# 3_Power_amp_Peripherals.net
KiCad netlist of a schematic drawn in Altium Designer
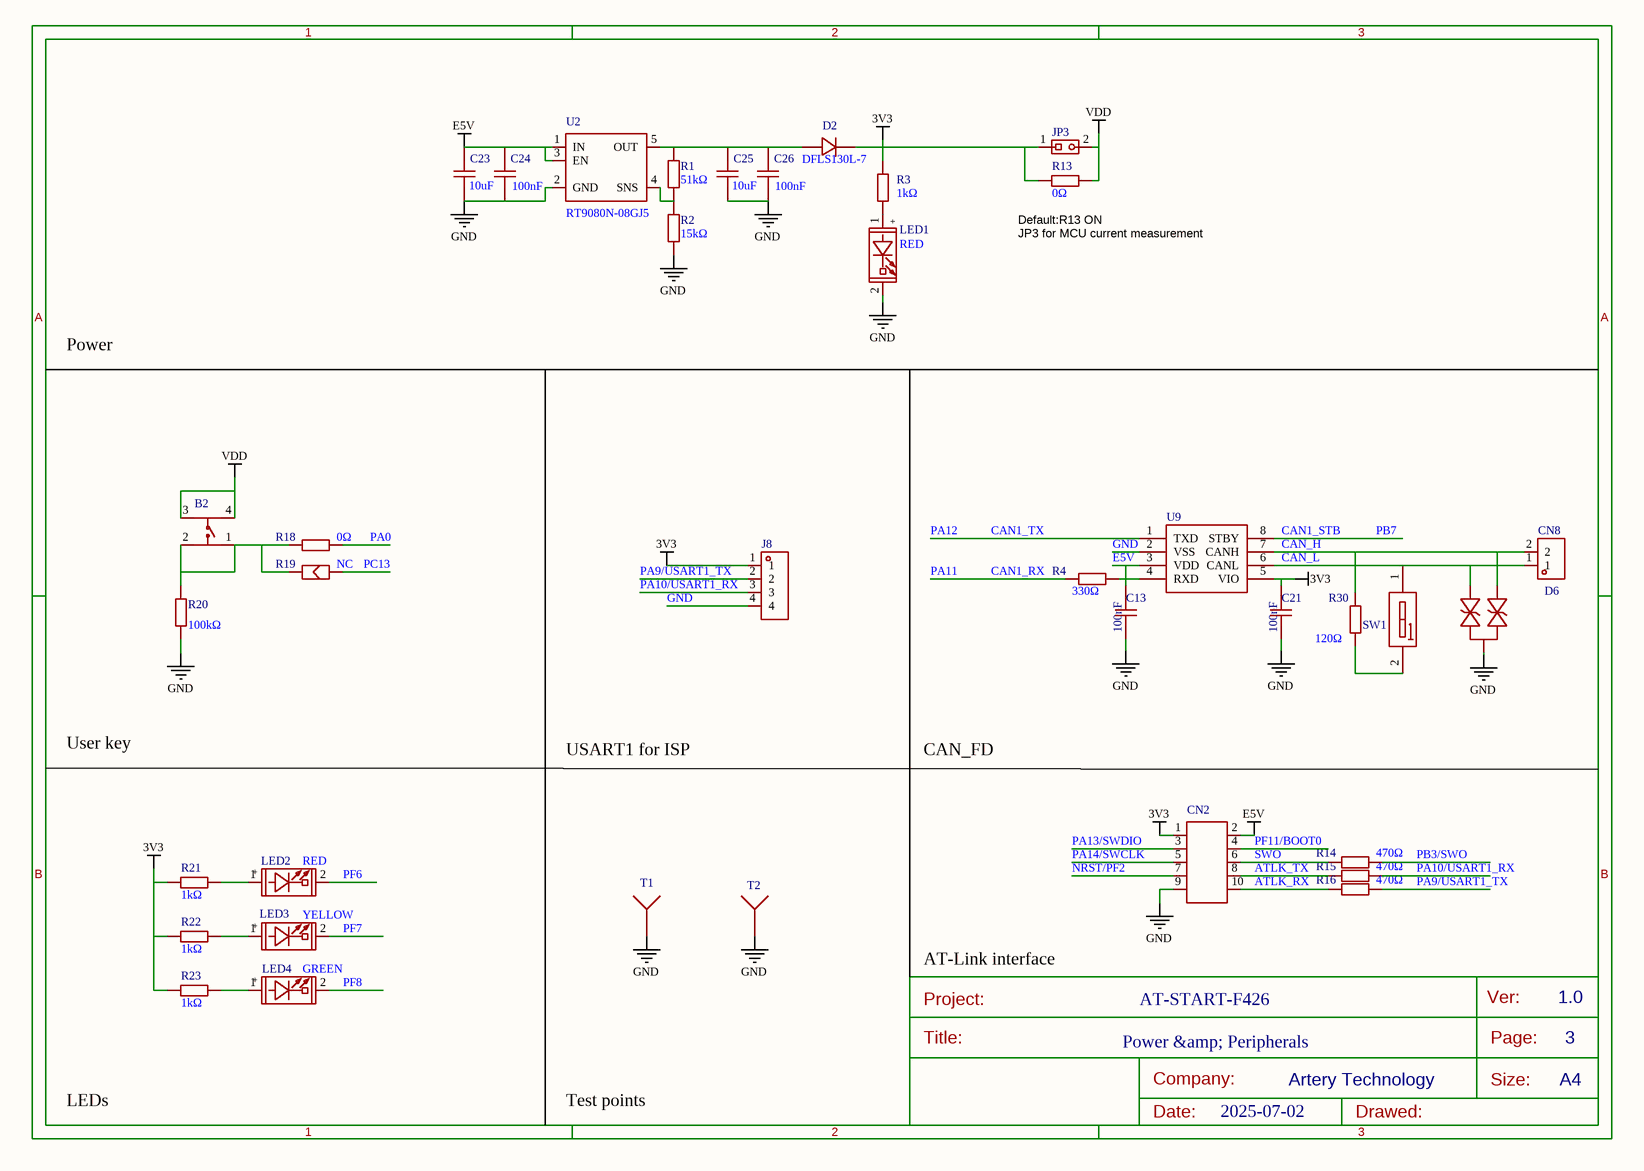
[diagram p0: 3_Power &amp; Peripherals.schdoc]

(export (version "E")
  (design (tool "Eeschema 10.0.6"))
  (components
    (comp (ref "B2")
      (value "TSA063G60-250")
      (footprint "KEY-SMD_4P-L6.1-W6.1-P4.50-LS9.0")
      (fields (field (name "MANUFACTURER") "BRIGHT(博瑞泰)"))
      (libsource (lib "altium-import") (part "root_0_mirrored_TSA063G60-250_"))
    )
    (comp (ref "C13")
      (value "100nF")
      (footprint "C0603")
      (fields
        (field (name "MANUFACTURER") "YAGEO(国巨)")
        (field (name "MANUFACTURER PART") "CC0603KRX7R9BB104")
        (field (name "ALTIUM_VALUE") "100nF")
        (field (name "TOLERANCE") "±10%")
      )
      (libsource (lib "altium-import") (part "root_1_CC0603KRX7R9BB104_"))
    )
    (comp (ref "C21")
      (value "100nF")
      (footprint "C0603")
      (fields
        (field (name "MANUFACTURER") "YAGEO(国巨)")
        (field (name "MANUFACTURER PART") "CC0603KRX7R9BB104")
        (field (name "ALTIUM_VALUE") "100nF")
        (field (name "TOLERANCE") "±10%")
      )
      (libsource (lib "altium-import") (part "root_1_CC0603KRX7R9BB104_"))
    )
    (comp (ref "C23")
      (value "10uF")
      (footprint "C0603")
      (fields
        (field (name "MANUFACTURER") "SAMSUNG(三星)")
        (field (name "MANUFACTURER PART") "CL10A106KP8NNNC")
        (field (name "TOLERANCE") "±10%")
      )
      (libsource (lib "altium-import") (part "root_3_CL10A106KP8NNNC_"))
    )
    (comp (ref "C24")
      (value "100nF")
      (footprint "C0603")
      (fields
        (field (name "MANUFACTURER") "YAGEO(国巨)")
        (field (name "MANUFACTURER PART") "CC0603KRX7R9BB104")
        (field (name "TOLERANCE") "±10%")
      )
      (libsource (lib "altium-import") (part "root_3_CC0603KRX7R9BB104_"))
    )
    (comp (ref "C25")
      (value "10uF")
      (footprint "C0603")
      (fields
        (field (name "MANUFACTURER") "SAMSUNG(三星)")
        (field (name "MANUFACTURER PART") "CL10A106KP8NNNC")
        (field (name "TOLERANCE") "±10%")
      )
      (libsource (lib "altium-import") (part "root_3_CL10A106KP8NNNC_"))
    )
    (comp (ref "C26")
      (value "100nF")
      (footprint "C0603")
      (fields
        (field (name "MANUFACTURER") "YAGEO(国巨)")
        (field (name "MANUFACTURER PART") "CC0603KRX7R9BB104")
        (field (name "TOLERANCE") "±10%")
      )
      (libsource (lib "altium-import") (part "root_3_CC0603KRX7R9BB104_"))
    )
    (comp (ref "CN2")
      (value "CON10")
      (footprint "HDR2X5")
      (libsource (lib "altium-import") (part "root_0_CON10_"))
    )
    (comp (ref "CN8")
      (value "KF301-5.0-2P")
      (footprint "CONN-TH_P5.00_KF301-5.0-2P")
      (fields (field (name "MANUFACTURER") "KEFA(科发)"))
      (libsource (lib "altium-import") (part "root_2_mirrored_KF301-5.0-2P_"))
    )
    (comp (ref "D2")
      (value "DFLS130L-7")
      (footprint "POWERDI-123_L2.8-W1.8-LS3.7-RD")
      (fields (field (name "MANUFACTURER") "DIODES(美台)") (field (name "PUBLISHER") "Altium Limited"))
      (libsource (lib "altium-import") (part "root_0_DFLS130L-7_"))
    )
    (comp (ref "D6")
      (value "PESD2CANFD24V-TR")
      (footprint "SOT-23-3_L2.9-W1.3-P1.90-LS2.4-BR")
      (fields (field (name "MANUFACTURER") "Nexperia(安世)"))
      (libsource (lib "altium-import") (part "root_2_PESD2CANFD24V-TR_"))
    )
    (comp (ref "J8")
      (value "PZ2.54-1*4-WZ")
      (footprint "HDR-TH_4P-P2.54-H-M-W7.7-P")
      (fields (field (name "MANUFACTURER") "ZHOURI(洲日)") (field (name "PUBLISHER") "Altium Limited"))
      (libsource (lib "altium-import") (part "root_0_PZ2.54-1*4-WZ_"))
    )
    (comp (ref "JP3")
      (value "1X2P_2.54M")
      (footprint "HDR1X2")
      (libsource (lib "altium-import") (part "root_0_1X2P_2.54M_"))
    )
    (comp (ref "LED1")
      (value "RED")
      (footprint "LED0603")
      (libsource (lib "altium-import") (part "root_3_RED_"))
    )
    (comp (ref "LED2")
      (value "RED")
      (footprint "LED0603")
      (libsource (lib "altium-import") (part "root_0_RED_"))
    )
    (comp (ref "LED3")
      (value "YELLOW")
      (footprint "LED0603")
      (libsource (lib "altium-import") (part "root_0_YELLOW_"))
    )
    (comp (ref "LED4")
      (value "GREEN")
      (footprint "LED0603")
      (libsource (lib "altium-import") (part "root_0_GREEN_"))
    )
    (comp (ref "R1")
      (value "51kΩ")
      (footprint "R0603")
      (fields
        (field (name "MANUFACTURER") "UNI-ROYAL(厚声)")
        (field (name "MANUFACTURER PART") "0603WAF5102T5E")
        (field (name "TOLERANCE") "±1%")
      )
      (libsource (lib "altium-import") (part "root_3_0603WAF5102T5E_"))
    )
    (comp (ref "R2")
      (value "15kΩ")
      (footprint "R0603")
      (fields
        (field (name "MANUFACTURER") "UNI-ROYAL(厚声)")
        (field (name "MANUFACTURER PART") "0603WAF1502T5E")
        (field (name "TOLERANCE") "±1%")
      )
      (libsource (lib "altium-import") (part "root_3_0603WAF1502T5E_"))
    )
    (comp (ref "R3")
      (value "1kΩ")
      (footprint "R0603")
      (fields
        (field (name "MANUFACTURER") "UNI-ROYAL(厚声)")
        (field (name "MANUFACTURER PART") "0603WAF1001T5E")
        (field (name "TOLERANCE") "±1%")
      )
      (libsource (lib "altium-import") (part "root_1_0603WAF1001T5E_"))
    )
    (comp (ref "R4")
      (value "330Ω")
      (footprint "R0603")
      (fields
        (field (name "MANUFACTURER") "UNI-ROYAL(厚声)")
        (field (name "MANUFACTURER PART") "0603WAF3300T5E")
        (field (name "ALTIUM_VALUE") "330Ω")
        (field (name "TOLERANCE") "±1%")
      )
      (libsource (lib "altium-import") (part "root_0_0603WAF3300T5E_"))
    )
    (comp (ref "R13")
      (value "0Ω")
      (footprint "SB-PAD_2")
      (fields
        (field (name "MANUFACTURER") "UNI-ROYAL(厚声)")
        (field (name "MANUFACTURER PART") "0603WAF0000T5E")
        (field (name "TOLERANCE") "±1%")
      )
      (libsource (lib "altium-import") (part "root_2_0603WAF0000T5E_"))
    )
    (comp (ref "R14")
      (value "470Ω")
      (footprint "R0603")
      (fields
        (field (name "MANUFACTURER") "UNI-ROYAL(厚声)")
        (field (name "MANUFACTURER PART") "0603WAF4700T5E")
        (field (name "TOLERANCE") "±1%")
      )
      (libsource (lib "altium-import") (part "root_2_0603WAF4700T5E_"))
    )
    (comp (ref "R15")
      (value "470Ω")
      (footprint "R0603")
      (fields
        (field (name "MANUFACTURER") "UNI-ROYAL(厚声)")
        (field (name "MANUFACTURER PART") "0603WAF4700T5E")
        (field (name "TOLERANCE") "±1%")
      )
      (libsource (lib "altium-import") (part "root_2_0603WAF4700T5E_"))
    )
    (comp (ref "R16")
      (value "470Ω")
      (footprint "R0603")
      (fields
        (field (name "MANUFACTURER") "UNI-ROYAL(厚声)")
        (field (name "MANUFACTURER PART") "0603WAF4700T5E")
        (field (name "TOLERANCE") "±1%")
      )
      (libsource (lib "altium-import") (part "root_2_0603WAF4700T5E_"))
    )
    (comp (ref "R18")
      (value "0Ω")
      (footprint "SB-PAD_2")
      (fields
        (field (name "MANUFACTURER") "UNI-ROYAL(厚声)")
        (field (name "MANUFACTURER PART") "0603WAF0000T5E")
        (field (name "TOLERANCE") "±1%")
      )
      (libsource (lib "altium-import") (part "root_2_0603WAF0000T5E_"))
    )
    (comp (ref "R19")
      (value "NC")
      (footprint "SB-PAD_2")
      (libsource (lib "altium-import") (part "root_2_SB_PAD_"))
    )
    (comp (ref "R20")
      (value "100kΩ")
      (footprint "R0603")
      (fields
        (field (name "MANUFACTURER") "UNI-ROYAL(厚声)")
        (field (name "MANUFACTURER PART") "0603WAF1003T5E")
        (field (name "TOLERANCE") "±1%")
      )
      (libsource (lib "altium-import") (part "root_3_0603WAF1003T5E_"))
    )
    (comp (ref "R21")
      (value "1kΩ")
      (footprint "R0603")
      (fields
        (field (name "MANUFACTURER") "UNI-ROYAL(厚声)")
        (field (name "MANUFACTURER PART") "0603WAF1001T5E")
        (field (name "TOLERANCE") "±1%")
      )
      (libsource (lib "altium-import") (part "root_2_0603WAF1001T5E_"))
    )
    (comp (ref "R22")
      (value "1kΩ")
      (footprint "R0603")
      (fields
        (field (name "MANUFACTURER") "UNI-ROYAL(厚声)")
        (field (name "MANUFACTURER PART") "0603WAF1001T5E")
        (field (name "TOLERANCE") "±1%")
      )
      (libsource (lib "altium-import") (part "root_2_0603WAF1001T5E_"))
    )
    (comp (ref "R23")
      (value "1kΩ")
      (footprint "R0603")
      (fields
        (field (name "MANUFACTURER") "UNI-ROYAL(厚声)")
        (field (name "MANUFACTURER PART") "0603WAF1001T5E")
        (field (name "TOLERANCE") "±1%")
      )
      (libsource (lib "altium-import") (part "root_2_0603WAF1001T5E_"))
    )
    (comp (ref "R30")
      (value "120Ω")
      (footprint "R0603")
      (fields
        (field (name "MANUFACTURER") "UNI-ROYAL(厚声)")
        (field (name "MANUFACTURER PART") "0603WAF1200T5E")
        (field (name "ALTIUM_VALUE") "120Ω")
        (field (name "TOLERANCE") "±1%")
      )
      (libsource (lib "altium-import") (part "root_1_0603WAF1200T5E_"))
    )
    (comp (ref "SW1")
      (value "DSWB01LHGET")
      (footprint "SW-TH_DSWB01LHGET")
      (fields (field (name "MANUFACTURER") "YE"))
      (libsource (lib "altium-import") (part "root_3_DSWB01LHGET_"))
    )
    (comp (ref "T1")
      (value "Test point")
      (footprint "TestPoint")
      (fields (field (name "PUBLISHER") "Altium Limited"))
      (libsource (lib "altium-import") (part "root_3_Test point_"))
    )
    (comp (ref "T2")
      (value "Test point")
      (footprint "TestPoint")
      (fields (field (name "PUBLISHER") "Altium Limited"))
      (libsource (lib "altium-import") (part "root_3_Test point_"))
    )
    (comp (ref "U2")
      (value "RT9080N-08GJ5")
      (footprint "SOT-23-5")
      (fields (field (name "LIBRARY NAME") "SCM_START_402F"))
      (libsource (lib "altium-import") (part "root_0_RT9080N-08GJ5_"))
    )
    (comp (ref "U9")
      (value "MCP2562FD-E/SN")
      (footprint "SOIC-8_L4.9-W3.9-P1.27-LS6.0-BL")
      (fields (field (name "MANUFACTURER") "MICROCHIP(美国微芯)"))
      (libsource (lib "altium-import") (part "root_0_MCP2562FD-E/SN_"))
    )
  )
  (nets
    (net (code "1") (name "/ATLK_RX") (class "Default")
      (node (ref "CN2") (pin "10") (pinfunction "10_10") (pintype "passive"))
      (node (ref "R16") (pin "2") (pinfunction "2_2") (pintype "passive"))
    )
    (net (code "2") (name "/ATLK_TX") (class "Default")
      (node (ref "CN2") (pin "8") (pinfunction "8_8") (pintype "passive"))
      (node (ref "R15") (pin "2") (pinfunction "2_2") (pintype "passive"))
    )
    (net (code "3") (name "/CAN1_RX") (class "Default")
      (node (ref "R4") (pin "1") (pinfunction "1_1") (pintype "passive"))
    )
    (net (code "4") (name "/CAN1_STB") (class "Default")
      (node (ref "U9") (pin "8") (pinfunction "STBY_8") (pintype "passive"))
    )
    (net (code "5") (name "/CAN1_TX") (class "Default")
      (node (ref "U9") (pin "1") (pinfunction "TXD_1") (pintype "passive"))
    )
    (net (code "6") (name "/CAN_H") (class "Default")
      (node (ref "CN8") (pin "2") (pinfunction "2_2") (pintype "passive"))
      (node (ref "D6") (pin "1") (pinfunction "1_1") (pintype "passive"))
      (node (ref "R30") (pin "2") (pinfunction "2_2") (pintype "passive"))
      (node (ref "U9") (pin "7") (pinfunction "CANH_7") (pintype "passive"))
    )
    (net (code "7") (name "/CAN_L") (class "Default")
      (node (ref "CN8") (pin "1") (pinfunction "1_1") (pintype "passive"))
      (node (ref "D6") (pin "2") (pinfunction "2_2") (pintype "passive"))
      (node (ref "SW1") (pin "1") (pinfunction "A1_1") (pintype "passive"))
      (node (ref "U9") (pin "6") (pinfunction "CANL_6") (pintype "passive"))
    )
    (net (code "8") (name "/NRST{slash}PF2") (class "Default")
      (node (ref "CN2") (pin "7") (pinfunction "7_7") (pintype "passive"))
    )
    (net (code "9") (name "/PA0") (class "Default")
      (node (ref "R18") (pin "1") (pinfunction "1_1") (pintype "passive"))
    )
    (net (code "10") (name "/PA9{slash}USART1_TX") (class "Default")
      (node (ref "J8") (pin "2") (pinfunction "2_2") (pintype "passive"))
      (node (ref "R16") (pin "1") (pinfunction "1_1") (pintype "passive"))
    )
    (net (code "11") (name "/PA10{slash}USART1_RX") (class "Default")
      (node (ref "J8") (pin "3") (pinfunction "3_3") (pintype "passive"))
      (node (ref "R15") (pin "1") (pinfunction "1_1") (pintype "passive"))
    )
    (net (code "12") (name "/PA13{slash}SWDIO") (class "Default")
      (node (ref "CN2") (pin "3") (pinfunction "3_3") (pintype "passive"))
    )
    (net (code "13") (name "/PA14{slash}SWCLK") (class "Default")
      (node (ref "CN2") (pin "5") (pinfunction "5_5") (pintype "passive"))
    )
    (net (code "14") (name "/PB3{slash}SWO") (class "Default")
      (node (ref "R14") (pin "1") (pinfunction "1_1") (pintype "passive"))
    )
    (net (code "15") (name "/PC13") (class "Default")
      (node (ref "R19") (pin "1") (pinfunction "1_1") (pintype "passive"))
    )
    (net (code "16") (name "/PF6") (class "Default")
      (node (ref "LED2") (pin "2") (pinfunction "CATHODE_2") (pintype "passive"))
    )
    (net (code "17") (name "/PF7") (class "Default")
      (node (ref "LED3") (pin "2") (pinfunction "CATHODE_2") (pintype "passive"))
    )
    (net (code "18") (name "/PF8") (class "Default")
      (node (ref "LED4") (pin "2") (pinfunction "CATHODE_2") (pintype "passive"))
    )
    (net (code "19") (name "/PF11{slash}BOOT0") (class "Default")
      (node (ref "CN2") (pin "4") (pinfunction "4_4") (pintype "passive"))
    )
    (net (code "20") (name "/SWO") (class "Default")
      (node (ref "CN2") (pin "6") (pinfunction "6_6") (pintype "passive"))
      (node (ref "R14") (pin "2") (pinfunction "2_2") (pintype "passive"))
    )
    (net (code "21") (name "3V3") (class "Default")
      (node (ref "C21") (pin "2") (pinfunction "2_2") (pintype "passive"))
      (node (ref "CN2") (pin "1") (pinfunction "1_1") (pintype "passive"))
      (node (ref "D2") (pin "1") (pinfunction "1_1") (pintype "passive"))
      (node (ref "J8") (pin "1") (pinfunction "1_1") (pintype "passive"))
      (node (ref "JP3") (pin "1") (pinfunction "1_1") (pintype "passive"))
      (node (ref "R13") (pin "2") (pinfunction "2_2") (pintype "passive"))
      (node (ref "R21") (pin "2") (pinfunction "2_2") (pintype "passive"))
      (node (ref "R22") (pin "2") (pinfunction "2_2") (pintype "passive"))
      (node (ref "R23") (pin "2") (pinfunction "2_2") (pintype "passive"))
      (node (ref "R3") (pin "2") (pinfunction "2_2") (pintype "passive"))
      (node (ref "U9") (pin "5") (pinfunction "VIO_5") (pintype "passive"))
    )
    (net (code "22") (name "E5V") (class "Default")
      (node (ref "C13") (pin "2") (pinfunction "2_2") (pintype "passive"))
      (node (ref "C23") (pin "1") (pinfunction "1_1") (pintype "passive"))
      (node (ref "C24") (pin "1") (pinfunction "1_1") (pintype "passive"))
      (node (ref "CN2") (pin "2") (pinfunction "2_2") (pintype "passive"))
      (node (ref "U2") (pin "1") (pinfunction "IN_1") (pintype "passive"))
      (node (ref "U2") (pin "3") (pinfunction "EN_3") (pintype "passive"))
      (node (ref "U9") (pin "3") (pinfunction "VDD_3") (pintype "passive"))
    )
    (net (code "23") (name "GND") (class "Default")
      (node (ref "C13") (pin "1") (pinfunction "1_1") (pintype "passive"))
      (node (ref "C21") (pin "1") (pinfunction "1_1") (pintype "passive"))
      (node (ref "C23") (pin "2") (pinfunction "2_2") (pintype "passive"))
      (node (ref "C24") (pin "2") (pinfunction "2_2") (pintype "passive"))
      (node (ref "C25") (pin "2") (pinfunction "2_2") (pintype "passive"))
      (node (ref "C26") (pin "2") (pinfunction "2_2") (pintype "passive"))
      (node (ref "CN2") (pin "9") (pinfunction "9_9") (pintype "passive"))
      (node (ref "D6") (pin "3") (pinfunction "3_3") (pintype "passive"))
      (node (ref "J8") (pin "4") (pinfunction "4_4") (pintype "passive"))
      (node (ref "LED1") (pin "2") (pinfunction "CATHODE_2") (pintype "passive"))
      (node (ref "R2") (pin "2") (pinfunction "2_2") (pintype "passive"))
      (node (ref "R20") (pin "2") (pinfunction "2_2") (pintype "passive"))
      (node (ref "T1") (pin "1") (pinfunction "1_1") (pintype "passive"))
      (node (ref "T2") (pin "1") (pinfunction "1_1") (pintype "passive"))
      (node (ref "U2") (pin "2") (pinfunction "GND_2") (pintype "passive"))
      (node (ref "U9") (pin "2") (pinfunction "VSS_2") (pintype "passive"))
    )
    (net (code "24") (name "Net-(B2-Pad1)") (class "Default")
      (node (ref "B2") (pin "1") (pinfunction "1_1") (pintype "passive"))
      (node (ref "B2") (pin "2") (pinfunction "2_2") (pintype "passive"))
      (node (ref "R18") (pin "2") (pinfunction "2_2") (pintype "passive"))
      (node (ref "R19") (pin "2") (pinfunction "2_2") (pintype "passive"))
      (node (ref "R20") (pin "1") (pinfunction "1_1") (pintype "passive"))
    )
    (net (code "25") (name "Net-(LED1-ANODE)") (class "Default")
      (node (ref "LED1") (pin "1") (pinfunction "ANODE_1") (pintype "passive"))
      (node (ref "R3") (pin "1") (pinfunction "1_1") (pintype "passive"))
    )
    (net (code "26") (name "Net-(LED2-ANODE)") (class "Default")
      (node (ref "LED2") (pin "1") (pinfunction "ANODE_1") (pintype "passive"))
      (node (ref "R21") (pin "1") (pinfunction "1_1") (pintype "passive"))
    )
    (net (code "27") (name "Net-(LED3-ANODE)") (class "Default")
      (node (ref "LED3") (pin "1") (pinfunction "ANODE_1") (pintype "passive"))
      (node (ref "R22") (pin "1") (pinfunction "1_1") (pintype "passive"))
    )
    (net (code "28") (name "Net-(LED4-ANODE)") (class "Default")
      (node (ref "LED4") (pin "1") (pinfunction "ANODE_1") (pintype "passive"))
      (node (ref "R23") (pin "1") (pinfunction "1_1") (pintype "passive"))
    )
    (net (code "29") (name "Net-(R30-Pad1)") (class "Default")
      (node (ref "R30") (pin "1") (pinfunction "1_1") (pintype "passive"))
      (node (ref "SW1") (pin "2") (pinfunction "2_2") (pintype "passive"))
    )
    (net (code "30") (name "Net-(U2-OUT)") (class "Default")
      (node (ref "C25") (pin "1") (pinfunction "1_1") (pintype "passive"))
      (node (ref "C26") (pin "1") (pinfunction "1_1") (pintype "passive"))
      (node (ref "D2") (pin "2") (pinfunction "2_2") (pintype "passive"))
      (node (ref "R1") (pin "1") (pinfunction "1_1") (pintype "passive"))
      (node (ref "U2") (pin "5") (pinfunction "OUT_5") (pintype "passive"))
    )
    (net (code "31") (name "Net-(U2-SNS)") (class "Default")
      (node (ref "R1") (pin "2") (pinfunction "2_2") (pintype "passive"))
      (node (ref "R2") (pin "1") (pinfunction "1_1") (pintype "passive"))
      (node (ref "U2") (pin "4") (pinfunction "SNS_4") (pintype "passive"))
    )
    (net (code "32") (name "Net-(U9-RXD)") (class "Default")
      (node (ref "R4") (pin "2") (pinfunction "2_2") (pintype "passive"))
      (node (ref "U9") (pin "4") (pinfunction "RXD_4") (pintype "passive"))
    )
    (net (code "33") (name "VDD") (class "Default")
      (node (ref "B2") (pin "3") (pinfunction "3_3") (pintype "passive"))
      (node (ref "B2") (pin "4") (pinfunction "4_4") (pintype "passive"))
      (node (ref "JP3") (pin "2") (pinfunction "2_2") (pintype "passive"))
      (node (ref "R13") (pin "1") (pinfunction "1_1") (pintype "passive"))
    )
  )
)
